# FDL-3_TRG.net
KiCad netlist of a schematic drawn in EAGLE
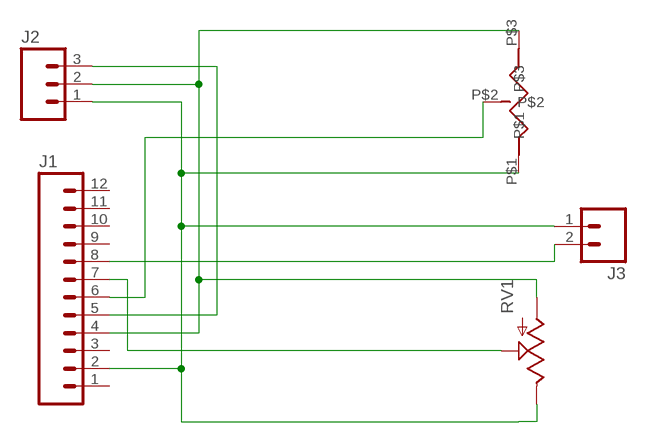
[diagram p0: schematic, sheet 1]

(export (version "E")
  (design (tool "Eeschema 10.0.6"))
  (components
    (comp (ref "J1")
      (value "M12LONGPADS")
      (footprint "eagle-import:1X12_LONGPADS")
      (libsource (lib "eagle-import") (part "M12LONGPADS"))
    )
    (comp (ref "J2")
      (value "M03LONGPADS")
      (footprint "eagle-import:1X03_LONGPADS")
      (libsource (lib "eagle-import") (part "M03LONGPADS"))
    )
    (comp (ref "J3")
      (value "M02PTH3")
      (footprint "eagle-import:1X02_LONGPADS")
      (libsource (lib "eagle-import") (part "M02PTH3"))
    )
    (comp (ref "RV1")
      (value "POTTRIM")
      (footprint "eagle-import:TRIM_POT")
      (libsource (lib "eagle-import") (part "POTTRIM"))
    )
    (comp (ref "U$1")
      (value "THRUHOLEPOT")
      (footprint "eagle-import:THRUHOLEPOT")
      (libsource (lib "eagle-import") (part "THRUHOLEPOT"))
    )
  )
  (nets
    (net (code "1") (name "Net-(J1-Pad5)") (class "Default")
      (node (ref "J1") (pin "5") (pinfunction "5_5") (pintype "passive"))
      (node (ref "J2") (pin "3") (pinfunction "3_3") (pintype "passive"))
    )
    (net (code "2") (name "Net-(J1-Pad6)") (class "Default")
      (node (ref "J1") (pin "6") (pinfunction "6_6") (pintype "passive"))
      (node (ref "U$1") (pin "P$2") (pinfunction "P$2_P$2") (pintype "bidirectional"))
    )
    (net (code "3") (name "Net-(J1-Pad8)") (class "Default")
      (node (ref "J1") (pin "8") (pinfunction "8_8") (pintype "passive"))
      (node (ref "J3") (pin "2") (pinfunction "2_2") (pintype "passive"))
    )
    (net (code "4") (name "Net-(RV1-A)") (class "Default")
      (node (ref "J1") (pin "4") (pinfunction "4_4") (pintype "passive"))
      (node (ref "J2") (pin "2") (pinfunction "2_2") (pintype "passive"))
      (node (ref "RV1") (pin "3") (pinfunction "A_3") (pintype "passive"))
      (node (ref "U$1") (pin "P$3") (pinfunction "P$3_P$3") (pintype "bidirectional"))
    )
    (net (code "5") (name "Net-(RV1-E)") (class "Default")
      (node (ref "J1") (pin "2") (pinfunction "2_2") (pintype "passive"))
      (node (ref "J2") (pin "1") (pinfunction "1_1") (pintype "passive"))
      (node (ref "J3") (pin "1") (pinfunction "1_1") (pintype "passive"))
      (node (ref "RV1") (pin "2") (pinfunction "E_2") (pintype "passive"))
      (node (ref "U$1") (pin "P$1") (pinfunction "P$1_P$1") (pintype "bidirectional"))
    )
    (net (code "6") (name "Net-(RV1-S)") (class "Default")
      (node (ref "J1") (pin "7") (pinfunction "7_7") (pintype "passive"))
      (node (ref "RV1") (pin "1") (pinfunction "S_1") (pintype "passive"))
    )
    (net (code "7") (name "unconnected-(J1-Pad1)") (class "Default")
      (node (ref "J1") (pin "1") (pinfunction "1_1") (pintype "passive"))
    )
    (net (code "8") (name "unconnected-(J1-Pad3)") (class "Default")
      (node (ref "J1") (pin "3") (pinfunction "3_3") (pintype "passive"))
    )
    (net (code "9") (name "unconnected-(J1-Pad9)") (class "Default")
      (node (ref "J1") (pin "9") (pinfunction "9_9") (pintype "passive"))
    )
    (net (code "10") (name "unconnected-(J1-Pad10)") (class "Default")
      (node (ref "J1") (pin "10") (pinfunction "10_10") (pintype "passive"))
    )
    (net (code "11") (name "unconnected-(J1-Pad11)") (class "Default")
      (node (ref "J1") (pin "11") (pinfunction "11_11") (pintype "passive"))
    )
    (net (code "12") (name "unconnected-(J1-Pad12)") (class "Default")
      (node (ref "J1") (pin "12") (pinfunction "12_12") (pintype "passive"))
    )
  )
)
